# Maze.net
KiCad netlist of a schematic drawn in EAGLE
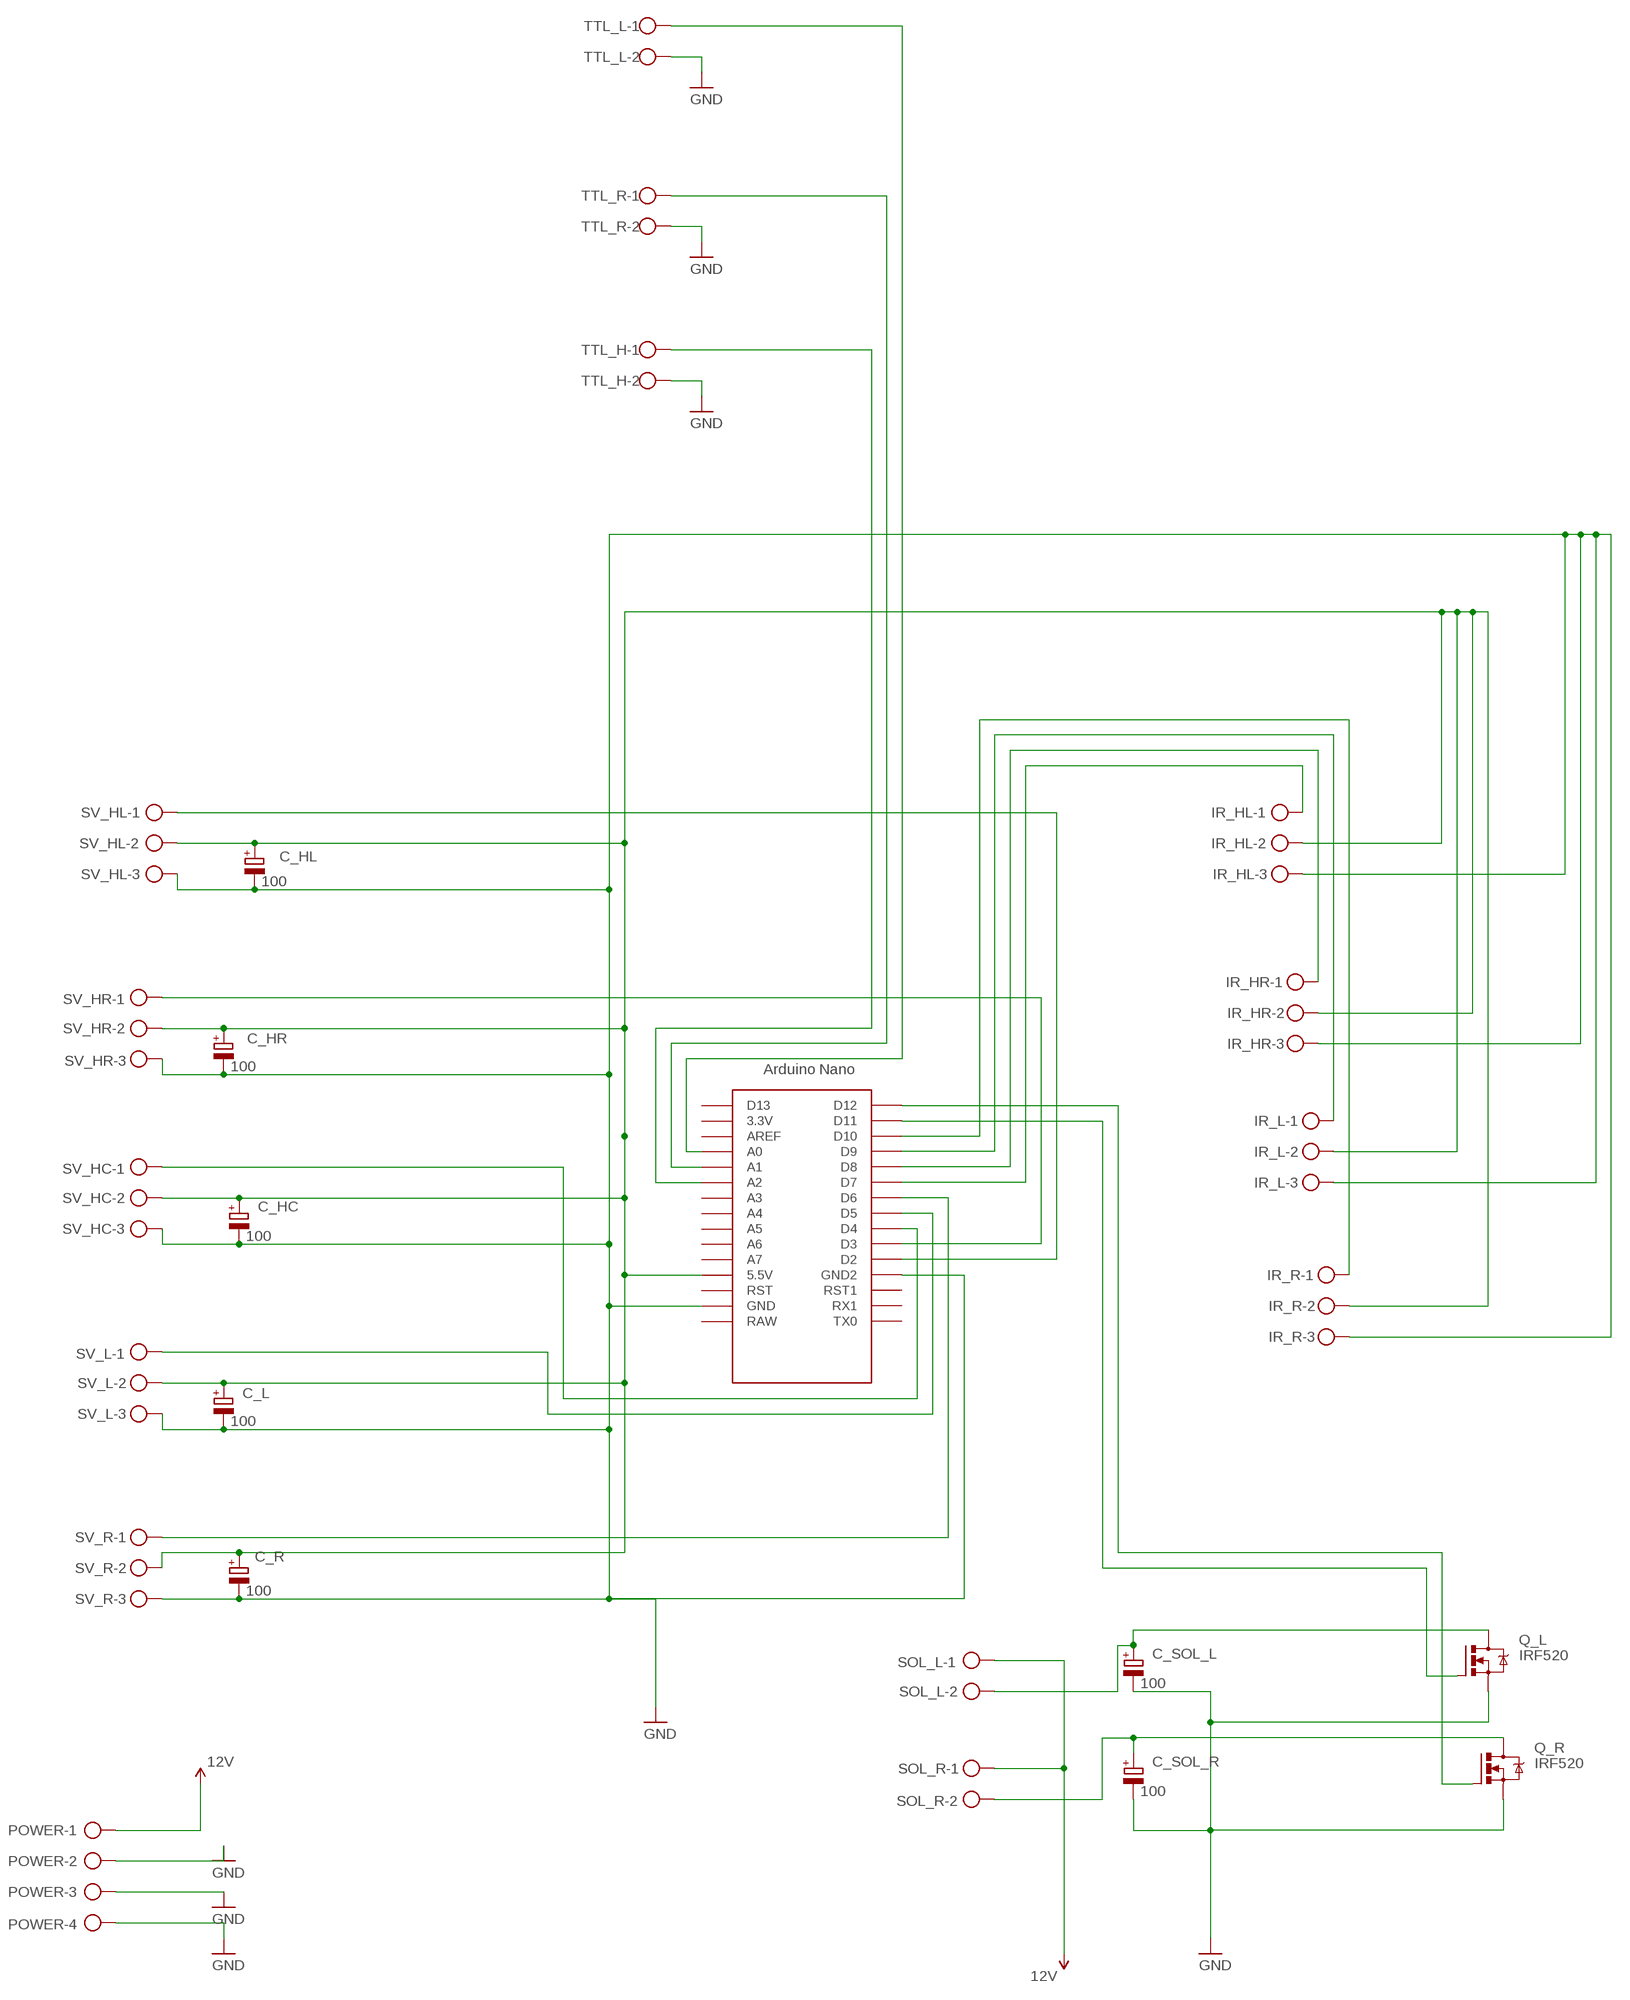
[diagram p0: schematic, sheet 1]

(export (version "E")
  (design (tool "Eeschema 10.0.6"))
  (components
    (comp (ref "C_HC")
      (value "100")
      (footprint "eagle-import:E2,5-6")
      (libsource (lib "eagle-import") (part "CPOL-EUE2.5-6"))
    )
    (comp (ref "C_HL")
      (value "100")
      (footprint "eagle-import:E2,5-6")
      (libsource (lib "eagle-import") (part "CPOL-EUE2.5-6"))
    )
    (comp (ref "C_HR")
      (value "100")
      (footprint "eagle-import:E2,5-6")
      (libsource (lib "eagle-import") (part "CPOL-EUE2.5-6"))
    )
    (comp (ref "C_L")
      (value "100")
      (footprint "eagle-import:E2,5-6")
      (libsource (lib "eagle-import") (part "CPOL-EUE2.5-6"))
    )
    (comp (ref "C_R")
      (value "100")
      (footprint "eagle-import:E2,5-6")
      (libsource (lib "eagle-import") (part "CPOL-EUE2.5-6"))
    )
    (comp (ref "C_SOL_L")
      (value "100")
      (footprint "eagle-import:E2,5-6")
      (libsource (lib "eagle-import") (part "CPOL-EUE2.5-6"))
    )
    (comp (ref "C_SOL_R")
      (value "100")
      (footprint "eagle-import:E2,5-6")
      (libsource (lib "eagle-import") (part "CPOL-EUE2.5-6"))
    )
    (comp (ref "IR_HL")
      (value "W237-103")
      (footprint "eagle-import:W237-103")
      (fields (field (name "MPN") "237-103"))
      (libsource (lib "eagle-import") (part "W237-103"))
    )
    (comp (ref "IR_HR")
      (value "W237-103")
      (footprint "eagle-import:W237-103")
      (fields (field (name "MPN") "237-103"))
      (libsource (lib "eagle-import") (part "W237-103"))
    )
    (comp (ref "IR_L")
      (value "W237-103")
      (footprint "eagle-import:W237-103")
      (fields (field (name "MPN") "237-103"))
      (libsource (lib "eagle-import") (part "W237-103"))
    )
    (comp (ref "IR_R")
      (value "W237-103")
      (footprint "eagle-import:W237-103")
      (fields (field (name "MPN") "237-103"))
      (libsource (lib "eagle-import") (part "W237-103"))
    )
    (comp (ref "POWER")
      (value "W237-4")
      (footprint "eagle-import:W237-4")
      (libsource (lib "eagle-import") (part "W237-4"))
    )
    (comp (ref "Q_L")
      (value "IRF520")
      (footprint "eagle-import:TO220BV")
      (libsource (lib "eagle-import") (part "IRF520"))
    )
    (comp (ref "Q_R")
      (value "IRF520")
      (footprint "eagle-import:TO220BV")
      (libsource (lib "eagle-import") (part "IRF520"))
    )
    (comp (ref "SOL_L")
      (value "W237-102")
      (footprint "eagle-import:W237-102")
      (fields (field (name "MPN") "237-102"))
      (libsource (lib "eagle-import") (part "W237-102"))
    )
    (comp (ref "SOL_R")
      (value "W237-102")
      (footprint "eagle-import:W237-102")
      (fields (field (name "MPN") "237-102"))
      (libsource (lib "eagle-import") (part "W237-102"))
    )
    (comp (ref "SV_HC")
      (value "W237-103")
      (footprint "eagle-import:W237-103")
      (fields (field (name "MPN") "237-103"))
      (libsource (lib "eagle-import") (part "W237-103"))
    )
    (comp (ref "SV_HL")
      (value "W237-103")
      (footprint "eagle-import:W237-103")
      (fields (field (name "MPN") "237-103") (field (name "SPICEPREFIX") "X"))
      (libsource (lib "eagle-import") (part "W237-103"))
    )
    (comp (ref "SV_HR")
      (value "W237-103")
      (footprint "eagle-import:W237-103")
      (fields (field (name "MPN") "237-103"))
      (libsource (lib "eagle-import") (part "W237-103"))
    )
    (comp (ref "SV_L")
      (value "W237-103")
      (footprint "eagle-import:W237-103")
      (fields (field (name "MPN") "237-103"))
      (libsource (lib "eagle-import") (part "W237-103"))
    )
    (comp (ref "SV_R")
      (value "W237-103")
      (footprint "eagle-import:W237-103")
      (fields (field (name "MPN") "237-103"))
      (libsource (lib "eagle-import") (part "W237-103"))
    )
    (comp (ref "TTL_H")
      (value "W237-102")
      (footprint "eagle-import:W237-102")
      (fields (field (name "MPN") "237-102"))
      (libsource (lib "eagle-import") (part "W237-102"))
    )
    (comp (ref "TTL_L")
      (value "W237-102")
      (footprint "eagle-import:W237-102")
      (fields (field (name "MPN") "237-102"))
      (libsource (lib "eagle-import") (part "W237-102"))
    )
    (comp (ref "TTL_R")
      (value "W237-102")
      (footprint "eagle-import:W237-102")
      (fields (field (name "MPN") "237-102"))
      (libsource (lib "eagle-import") (part "W237-102"))
    )
    (comp (ref "U$1")
      (value "NANO")
      (footprint "eagle-import:NANO")
      (libsource (lib "eagle-import") (part "NANO"))
    )
  )
  (nets
    (net (code "1") (name "12V") (class "Default")
      (node (ref "POWER") (pin "1") (pinfunction "KL_1") (pintype "passive"))
      (node (ref "SOL_L") (pin "1") (pinfunction "KL_1") (pintype "passive"))
      (node (ref "SOL_R") (pin "1") (pinfunction "KL_1") (pintype "passive"))
    )
    (net (code "2") (name "GND") (class "Default")
      (node (ref "C_HC") (pin "-") (pinfunction "-_-") (pintype "passive"))
      (node (ref "C_HL") (pin "-") (pinfunction "-_-") (pintype "passive"))
      (node (ref "C_HR") (pin "-") (pinfunction "-_-") (pintype "passive"))
      (node (ref "C_L") (pin "-") (pinfunction "-_-") (pintype "passive"))
      (node (ref "C_R") (pin "-") (pinfunction "-_-") (pintype "passive"))
      (node (ref "C_SOL_L") (pin "-") (pinfunction "-_-") (pintype "passive"))
      (node (ref "C_SOL_R") (pin "-") (pinfunction "-_-") (pintype "passive"))
      (node (ref "IR_HL") (pin "3") (pinfunction "KL_3") (pintype "passive"))
      (node (ref "IR_HR") (pin "3") (pinfunction "KL_3") (pintype "passive"))
      (node (ref "IR_L") (pin "3") (pinfunction "KL_3") (pintype "passive"))
      (node (ref "IR_R") (pin "3") (pinfunction "KL_3") (pintype "passive"))
      (node (ref "POWER") (pin "2") (pinfunction "KL_2") (pintype "passive"))
      (node (ref "POWER") (pin "3") (pinfunction "KL_3") (pintype "passive"))
      (node (ref "POWER") (pin "4") (pinfunction "KL_4") (pintype "passive"))
      (node (ref "Q_L") (pin "S") (pinfunction "S_S") (pintype "passive"))
      (node (ref "Q_R") (pin "S") (pinfunction "S_S") (pintype "passive"))
      (node (ref "SV_HC") (pin "3") (pinfunction "KL_3") (pintype "passive"))
      (node (ref "SV_HL") (pin "3") (pinfunction "KL_3") (pintype "passive"))
      (node (ref "SV_HR") (pin "3") (pinfunction "KL_3") (pintype "passive"))
      (node (ref "SV_L") (pin "3") (pinfunction "KL_3") (pintype "passive"))
      (node (ref "SV_R") (pin "3") (pinfunction "KL_3") (pintype "passive"))
      (node (ref "TTL_H") (pin "2") (pinfunction "KL_2") (pintype "passive"))
      (node (ref "TTL_L") (pin "2") (pinfunction "KL_2") (pintype "passive"))
      (node (ref "TTL_R") (pin "2") (pinfunction "KL_2") (pintype "passive"))
      (node (ref "U$1") (pin "GND") (pinfunction "GND_GND") (pintype "bidirectional"))
      (node (ref "U$1") (pin "GND1") (pinfunction "GND2_GND1") (pintype "bidirectional"))
    )
    (net (code "3") (name "Net-(IR_HLA-KL)") (class "Default")
      (node (ref "IR_HL") (pin "1") (pinfunction "KL_1") (pintype "passive"))
      (node (ref "U$1") (pin "D7") (pinfunction "D7_D7") (pintype "bidirectional"))
    )
    (net (code "4") (name "Net-(IR_HLB-KL)") (class "Default")
      (node (ref "C_HC") (pin "+") (pinfunction "+_+") (pintype "passive"))
      (node (ref "C_HL") (pin "+") (pinfunction "+_+") (pintype "passive"))
      (node (ref "C_HR") (pin "+") (pinfunction "+_+") (pintype "passive"))
      (node (ref "C_L") (pin "+") (pinfunction "+_+") (pintype "passive"))
      (node (ref "C_R") (pin "+") (pinfunction "+_+") (pintype "passive"))
      (node (ref "IR_HL") (pin "2") (pinfunction "KL_2") (pintype "passive"))
      (node (ref "IR_HR") (pin "2") (pinfunction "KL_2") (pintype "passive"))
      (node (ref "IR_L") (pin "2") (pinfunction "KL_2") (pintype "passive"))
      (node (ref "IR_R") (pin "2") (pinfunction "KL_2") (pintype "passive"))
      (node (ref "SV_HC") (pin "2") (pinfunction "KL_2") (pintype "passive"))
      (node (ref "SV_HL") (pin "2") (pinfunction "KL_2") (pintype "passive"))
      (node (ref "SV_HR") (pin "2") (pinfunction "KL_2") (pintype "passive"))
      (node (ref "SV_L") (pin "2") (pinfunction "KL_2") (pintype "passive"))
      (node (ref "SV_R") (pin "2") (pinfunction "KL_2") (pintype "passive"))
      (node (ref "U$1") (pin "5V") (pinfunction "5.5V_5V") (pintype "bidirectional"))
    )
    (net (code "5") (name "Net-(IR_HRA-KL)") (class "Default")
      (node (ref "IR_HR") (pin "1") (pinfunction "KL_1") (pintype "passive"))
      (node (ref "U$1") (pin "D8") (pinfunction "D8_D8") (pintype "bidirectional"))
    )
    (net (code "6") (name "Net-(IR_LA-KL)") (class "Default")
      (node (ref "IR_L") (pin "1") (pinfunction "KL_1") (pintype "passive"))
      (node (ref "U$1") (pin "D9") (pinfunction "D9_D9") (pintype "bidirectional"))
    )
    (net (code "7") (name "Net-(IR_RA-KL)") (class "Default")
      (node (ref "IR_R") (pin "1") (pinfunction "KL_1") (pintype "passive"))
      (node (ref "U$1") (pin "D10") (pinfunction "D10_D10") (pintype "bidirectional"))
    )
    (net (code "8") (name "Net-(Q_L-PadG)") (class "Default")
      (node (ref "Q_L") (pin "G") (pinfunction "G_G") (pintype "passive"))
      (node (ref "U$1") (pin "D11") (pinfunction "D11_D11") (pintype "bidirectional"))
    )
    (net (code "9") (name "Net-(Q_R-PadG)") (class "Default")
      (node (ref "Q_R") (pin "G") (pinfunction "G_G") (pintype "passive"))
      (node (ref "U$1") (pin "D12") (pinfunction "D12_D12") (pintype "bidirectional"))
    )
    (net (code "10") (name "Net-(SOL_LB-KL)") (class "Default")
      (node (ref "C_SOL_L") (pin "+") (pinfunction "+_+") (pintype "passive"))
      (node (ref "Q_L") (pin "D") (pinfunction "D_D") (pintype "passive"))
      (node (ref "SOL_L") (pin "2") (pinfunction "KL_2") (pintype "passive"))
    )
    (net (code "11") (name "Net-(SOL_RB-KL)") (class "Default")
      (node (ref "C_SOL_R") (pin "+") (pinfunction "+_+") (pintype "passive"))
      (node (ref "Q_R") (pin "D") (pinfunction "D_D") (pintype "passive"))
      (node (ref "SOL_R") (pin "2") (pinfunction "KL_2") (pintype "passive"))
    )
    (net (code "12") (name "Net-(SV_HCA-KL)") (class "Default")
      (node (ref "SV_HC") (pin "1") (pinfunction "KL_1") (pintype "passive"))
      (node (ref "U$1") (pin "D4") (pinfunction "D4_D4") (pintype "bidirectional"))
    )
    (net (code "13") (name "Net-(SV_HLA-KL)") (class "Default")
      (node (ref "SV_HL") (pin "1") (pinfunction "KL_1") (pintype "passive"))
      (node (ref "U$1") (pin "D2") (pinfunction "D2_D2") (pintype "bidirectional"))
    )
    (net (code "14") (name "Net-(SV_HRA-KL)") (class "Default")
      (node (ref "SV_HR") (pin "1") (pinfunction "KL_1") (pintype "passive"))
      (node (ref "U$1") (pin "D3") (pinfunction "D3_D3") (pintype "bidirectional"))
    )
    (net (code "15") (name "Net-(SV_LA-KL)") (class "Default")
      (node (ref "SV_L") (pin "1") (pinfunction "KL_1") (pintype "passive"))
      (node (ref "U$1") (pin "D5") (pinfunction "D5_D5") (pintype "bidirectional"))
    )
    (net (code "16") (name "Net-(SV_RA-KL)") (class "Default")
      (node (ref "SV_R") (pin "1") (pinfunction "KL_1") (pintype "passive"))
      (node (ref "U$1") (pin "D6") (pinfunction "D6_D6") (pintype "bidirectional"))
    )
    (net (code "17") (name "Net-(TTL_HA-KL)") (class "Default")
      (node (ref "TTL_H") (pin "1") (pinfunction "KL_1") (pintype "passive"))
      (node (ref "U$1") (pin "A2") (pinfunction "A2_A2") (pintype "bidirectional"))
    )
    (net (code "18") (name "Net-(TTL_LA-KL)") (class "Default")
      (node (ref "TTL_L") (pin "1") (pinfunction "KL_1") (pintype "passive"))
      (node (ref "U$1") (pin "A0") (pinfunction "A0_A0") (pintype "bidirectional"))
    )
    (net (code "19") (name "Net-(TTL_RA-KL)") (class "Default")
      (node (ref "TTL_R") (pin "1") (pinfunction "KL_1") (pintype "passive"))
      (node (ref "U$1") (pin "A1") (pinfunction "A1_A1") (pintype "bidirectional"))
    )
    (net (code "20") (name "unconnected-(U$1-Pad3.3V)") (class "Default")
      (node (ref "U$1") (pin "3.3V") (pinfunction "3.3V_3.3V") (pintype "bidirectional"))
    )
    (net (code "21") (name "unconnected-(U$1-PadA3)") (class "Default")
      (node (ref "U$1") (pin "A3") (pinfunction "A3_A3") (pintype "bidirectional"))
    )
    (net (code "22") (name "unconnected-(U$1-PadA4)") (class "Default")
      (node (ref "U$1") (pin "A4") (pinfunction "A4_A4") (pintype "bidirectional"))
    )
    (net (code "23") (name "unconnected-(U$1-PadA5)") (class "Default")
      (node (ref "U$1") (pin "A5") (pinfunction "A5_A5") (pintype "bidirectional"))
    )
    (net (code "24") (name "unconnected-(U$1-PadA6)") (class "Default")
      (node (ref "U$1") (pin "A6") (pinfunction "A6_A6") (pintype "bidirectional"))
    )
    (net (code "25") (name "unconnected-(U$1-PadA7)") (class "Default")
      (node (ref "U$1") (pin "A7") (pinfunction "A7_A7") (pintype "bidirectional"))
    )
    (net (code "26") (name "unconnected-(U$1-PadAREF)") (class "Default")
      (node (ref "U$1") (pin "AREF") (pinfunction "AREF_AREF") (pintype "bidirectional"))
    )
    (net (code "27") (name "unconnected-(U$1-PadD13)") (class "Default")
      (node (ref "U$1") (pin "D13") (pinfunction "D13_D13") (pintype "bidirectional"))
    )
    (net (code "28") (name "unconnected-(U$1-PadICSP1)") (class "Default")
      (node (ref "U$1") (pin "ICSP1") (pinfunction "ICSP1_ICSP1") (pintype "bidirectional"))
    )
    (net (code "29") (name "unconnected-(U$1-PadICSP2)") (class "Default")
      (node (ref "U$1") (pin "ICSP2") (pinfunction "ICSP2_ICSP2") (pintype "bidirectional"))
    )
    (net (code "30") (name "unconnected-(U$1-PadICSP3)") (class "Default")
      (node (ref "U$1") (pin "ICSP3") (pinfunction "ICSP3_ICSP3") (pintype "bidirectional"))
    )
    (net (code "31") (name "unconnected-(U$1-PadICSP4)") (class "Default")
      (node (ref "U$1") (pin "ICSP4") (pinfunction "ICSP4_ICSP4") (pintype "bidirectional"))
    )
    (net (code "32") (name "unconnected-(U$1-PadICSP5)") (class "Default")
      (node (ref "U$1") (pin "ICSP5") (pinfunction "ICSP5_ICSP5") (pintype "bidirectional"))
    )
    (net (code "33") (name "unconnected-(U$1-PadICSP6)") (class "Default")
      (node (ref "U$1") (pin "ICSP6") (pinfunction "ICSP6_ICSP6") (pintype "bidirectional"))
    )
    (net (code "34") (name "unconnected-(U$1-PadRAW)") (class "Default")
      (node (ref "U$1") (pin "RAW") (pinfunction "RAW_RAW") (pintype "bidirectional"))
    )
    (net (code "35") (name "unconnected-(U$1-PadRST)") (class "Default")
      (node (ref "U$1") (pin "RST") (pinfunction "RST_RST") (pintype "bidirectional"))
    )
    (net (code "36") (name "unconnected-(U$1-PadRST1)") (class "Default")
      (node (ref "U$1") (pin "RST1") (pinfunction "RST1_RST1") (pintype "bidirectional"))
    )
    (net (code "37") (name "unconnected-(U$1-PadRX1)") (class "Default")
      (node (ref "U$1") (pin "RX1") (pinfunction "RX1_RX1") (pintype "bidirectional"))
    )
    (net (code "38") (name "unconnected-(U$1-PadTX0)") (class "Default")
      (node (ref "U$1") (pin "TX0") (pinfunction "TX0_TX0") (pintype "bidirectional"))
    )
  )
)
